# Amp.net
KiCad netlist of a schematic drawn in Altium Designer
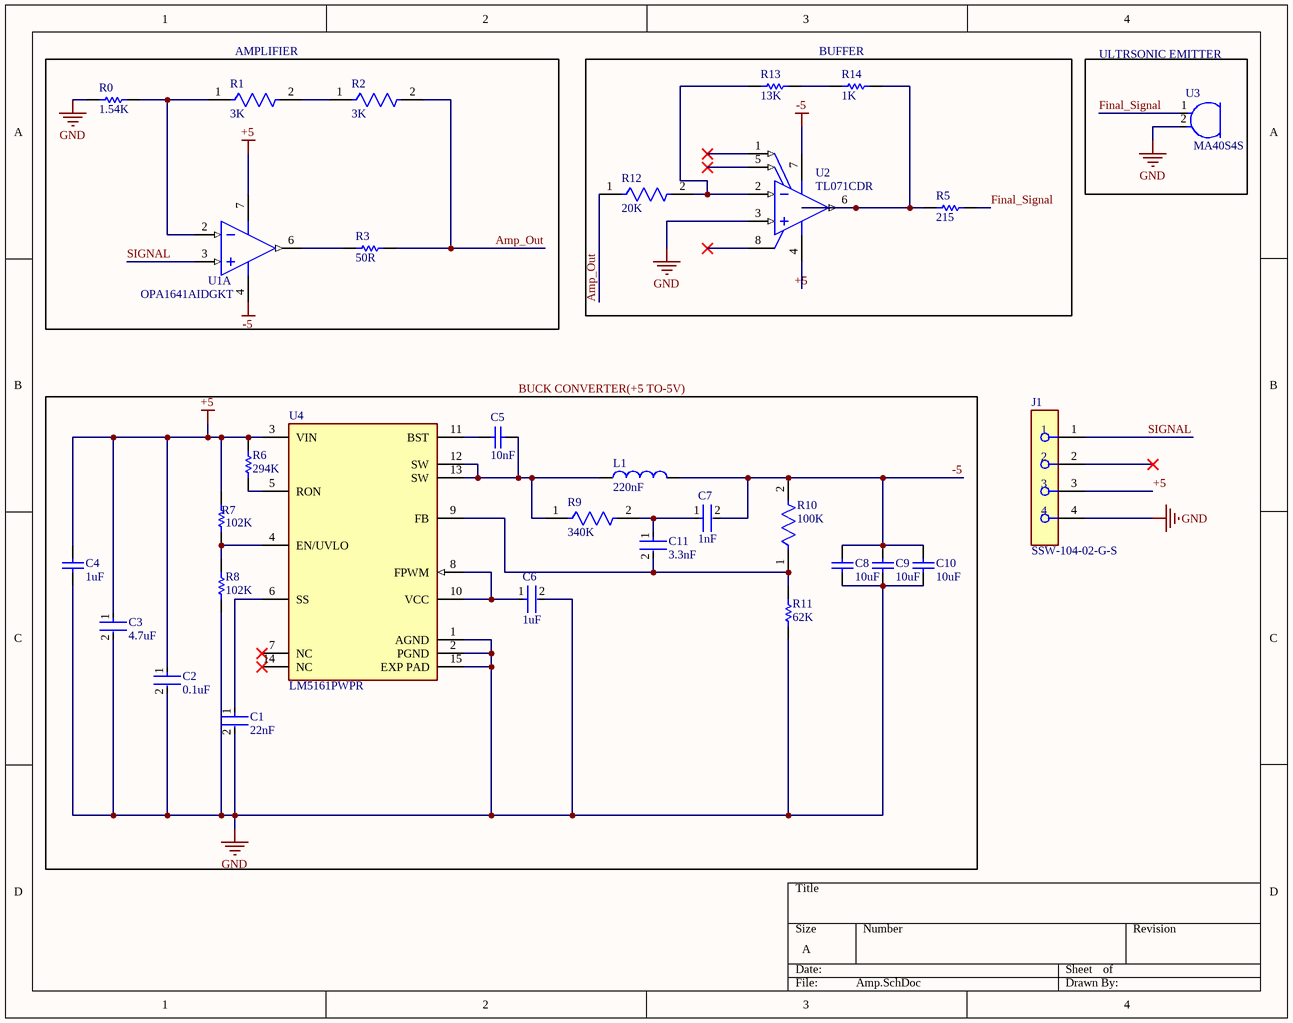
[diagram p0: Amp.SchDoc]

(export (version "E")
  (design (tool "Eeschema 10.0.6"))
  (components
    (comp (ref "C1")
      (value "22nF")
      (footprint "FP-CGA4J-MFG")
      (description "Cap Ceramic 22nF 50V C0G 5% Pad SMD 0805 +125°C Automotive T/R")
      (fields (field (name "TOLERANCE") "5%"))
      (libsource (lib "Altium Content Vault") (part "b4654b650e69147ec39a6b967a45e02"))
    )
    (comp (ref "C2")
      (value "0.1uF")
      (footprint "FP-CC0805-0_85-MFG")
      (description "CAP CER 0.1UF 25V X7R 0805")
      (fields (field (name "MANUFACTURER PART NUMBER") "CC0805KRX7R8BB104") (field (name "TOLERANCE") "0.1"))
      (libsource (lib "Altium Content Vault") (part "11868f565c42a9108669ba33697ecf6"))
    )
    (comp (ref "C3")
      (value "4.7uF")
      (footprint "FP-GRM31C-0_2-e0_3_0_8-IPC_C")
      (description "Chip Multilayer Ceramic Capacitors for General Purpose, 1206, 4.7uF, X7R, 15%, 10%, 50V")
      (fields (field (name "VOLTAGE") "50V") (field (name "TOLERANCE") "10%"))
      (libsource (lib "Altium Content Vault") (part "02cd4be3c70576c341d710602a673aa"))
    )
    (comp (ref "C4")
      (value "1uF")
      (footprint "CAPC3216X180X50ML20T25")
      (description "Chip Capacitor, 1 uF, +/- 10%, 25 V, -55 to 125 degC, 1206 (3216 Metric), RoHS, Tape and Reel")
      (fields (field (name "MANUFACTURER") "Kemet") (field (name "TOLERANCE") "10%"))
      (libsource (lib "Altium Content Vault") (part "CAP-NP-2"))
    )
    (comp (ref "C5")
      (value "10nF")
      (footprint "CAPC1005X55X25LL05T10")
      (description "Chip Capacitor, 10 nF, 16 V, 10%, -55 to 125 degC, 0402 (1005 Metric), RoHS, Tape and Reel")
      (fields (field (name "MANUFACTURER") "Murata"))
      (libsource (lib "Altium Content Vault") (part "CAP-NP-2"))
    )
    (comp (ref "C6")
      (value "1uF")
      (footprint "FP-CGA3E-0_3-0_1-MFG")
      (description "Cap Ceramic 1uF 35V X7R 10% Pad SMD 0603 +125°C Automotive T/R")
      (fields (field (name "TOLERANCE") "10%"))
      (libsource (lib "Altium Content Vault") (part "b4654b650e69147ec39a6b967a45e02"))
    )
    (comp (ref "C7")
      (value "1nF")
      (footprint "FP-CGA2B-MFG")
      (description "Cap Ceramic 1nF 50V X7R 10% Pad SMD 0402 +125°C Automotive T/R")
      (fields (field (name "TOLERANCE") "10%"))
      (libsource (lib "Altium Content Vault") (part "b4654b650e69147ec39a6b967a45e02"))
    )
    (comp (ref "C8")
      (value "10uF")
      (footprint "CAPC3216X180X55LL20T25")
      (description "Chip Capacitor, 10 uF, +/- 10%, 16 V, -55 to 125 degC, 1206 (3216 Metric), RoHS, Tape and Reel")
      (fields (field (name "MANUFACTURER") "Murata") (field (name "TOLERANCE") "±10%"))
      (libsource (lib "Altium Content Vault") (part "CAP-NP-2"))
    )
    (comp (ref "C9")
      (value "10uF")
      (footprint "CAPC3216X180X55LL20T25")
      (description "Chip Capacitor, 10 uF, +/- 10%, 16 V, -55 to 125 degC, 1206 (3216 Metric), RoHS, Tape and Reel")
      (fields (field (name "MANUFACTURER") "Murata") (field (name "TOLERANCE") "±10%"))
      (libsource (lib "Altium Content Vault") (part "CAP-NP-2"))
    )
    (comp (ref "C10")
      (value "10uF")
      (footprint "CAPC3216X180X55LL20T25")
      (description "Chip Capacitor, 10 uF, +/- 10%, 16 V, -55 to 125 degC, 1206 (3216 Metric), RoHS, Tape and Reel")
      (fields (field (name "MANUFACTURER") "Murata") (field (name "TOLERANCE") "±10%"))
      (libsource (lib "Altium Content Vault") (part "CAP-NP-2"))
    )
    (comp (ref "C11")
      (value "3.3nF")
      (footprint "FP-CL31-IPC_C")
      (description "Cap Ceramic 3.3nF 50V X7R ±10% SMD 1206 +125°C Embossed T/R")
      (fields (field (name "TOLERANCE") "10%") (field (name "VOLTAGE") "50V"))
      (libsource (lib "Altium Content Vault") (part "b4654b650e69147ec39a6b967a45e02"))
    )
    (comp (ref "J1")
      (value "SSW-104-02-G-S")
      (footprint "FP-SSW-104-02-G-S-MFG")
      (libsource (lib "Altium Content Vault") (part "56792406a6bd5c25e158f553ecd1aa7"))
    )
    (comp (ref "L1")
      (value "220nF")
      (footprint "WE-HCF_2920")
      (description "74437529203221 WE-HCF High Current Inductor, 220uH, 8.8A, 2.8MHz, 36.45mOhm")
      (libsource (lib "Altium Content Vault") (part "Inductor - 1"))
    )
    (comp (ref "R0")
      (value "1.54K")
      (footprint "RESC2013X70X40LL20T20")
      (fields (field (name "MANUFACTURER") "Panasonic") (field (name "PART NUMBER") "ERJ-6ENF1541V"))
      (libsource (lib "Altium Content Vault") (part "RES"))
    )
    (comp (ref "R1")
      (value "3K")
      (footprint "FP-RC2012-MFG")
      (description "Res Thick Film 0805 3kΩ 1% 0.125W ±100ppm/°C Molded SMD T/R")
      (fields (field (name "TOLERANCE") "1%"))
      (libsource (lib "Altium Content Vault") (part "1029c3af85768c4190bb7ad29bc67b5"))
    )
    (comp (ref "R2")
      (value "3K")
      (footprint "FP-RC2012-MFG")
      (description "Res Thick Film 0805 3kΩ 1% 0.125W ±100ppm/°C Molded SMD T/R")
      (fields (field (name "TOLERANCE") "1%"))
      (libsource (lib "Altium Content Vault") (part "1029c3af85768c4190bb7ad29bc67b5"))
    )
    (comp (ref "R3")
      (value "50R")
      (footprint "RESC2013X70X40LL20T20")
      (fields (field (name "PART NUMBER") "ERJ-6GEYJ510V") (field (name "MANUFACTURER") "Panasonic"))
      (libsource (lib "Altium Content Vault") (part "RES"))
    )
    (comp (ref "R5")
      (value "215")
      (footprint "RESC2013X70X40NL20T20")
      (fields (field (name "MANUFACTURER") "Panasonic") (field (name "PART NUMBER") "ERJ-6ENF2150V"))
      (libsource (lib "Altium Content Vault") (part "RES"))
    )
    (comp (ref "R6")
      (value "294K")
      (footprint "RESC1005X40X25LL05T05")
      (fields (field (name "PART NUMBER") "CRCW0402294KFKED") (field (name "MANUFACTURER") "Vishay Dale"))
      (libsource (lib "Altium Content Vault") (part "RES"))
    )
    (comp (ref "R7")
      (value "102K")
      (footprint "RESC2013X60X35LL10T20")
      (fields (field (name "PART NUMBER") "RC0805FR-07105KL") (field (name "MANUFACTURER") "Yageo"))
      (libsource (lib "Altium Content Vault") (part "RES"))
    )
    (comp (ref "R8")
      (value "102K")
      (footprint "RESC2013X60X35LL10T20")
      (fields (field (name "PART NUMBER") "RC0805FR-07105KL") (field (name "MANUFACTURER") "Yageo"))
      (libsource (lib "Altium Content Vault") (part "RES"))
    )
    (comp (ref "R9")
      (value "340K")
      (footprint "FP-CRCW0402-e3-MFG")
      (description "RES Thick Film, 340kΩ, 1%, 0.063W, 100ppm/°C, 0402")
      (fields (field (name "TOLERANCE") "1%"))
      (libsource (lib "Altium Content Vault") (part "1029c3af85768c4190bb7ad29bc67b5"))
    )
    (comp (ref "R10")
      (value "100K")
      (footprint "FP-RC0603-0_55-MFG")
      (description "RES SMD 100K OHM 1% 1/10W 0603")
      (fields (field (name "TOLERANCE") "1%"))
      (libsource (lib "Altium Content Vault") (part "1029c3af85768c4190bb7ad29bc67b5"))
    )
    (comp (ref "R11")
      (value "62K")
      (footprint "RESC1608X55X25NL10T15")
      (fields (field (name "MANUFACTURER") "Yageo") (field (name "PART NUMBER") "RC0603FR-0762KL"))
      (libsource (lib "Altium Content Vault") (part "RES"))
    )
    (comp (ref "R12")
      (value "20K")
      (footprint "FP-RT0805-MFG")
      (description "RES SMD 20K OHM 1% 1/8W 0805")
      (fields
        (field (name "MANUFACTURER") "Yageo")
        (field (name "MANUFACTURER PART NUMBER") "RT0805FRE0720KL")
      )
      (libsource (lib "Altium Content Vault") (part "1029c3af85768c4190bb7ad29bc67b5"))
    )
    (comp (ref "R13")
      (value "13K")
      (footprint "RESC2013X70X40NL20T20")
      (fields (field (name "PART NUMBER") "ERJ-6ENF1302V") (field (name "MANUFACTURER") "Panasonic"))
      (libsource (lib "Altium Content Vault") (part "RES"))
    )
    (comp (ref "R14")
      (value "1K")
      (footprint "RESC2013X70X40ML20T20")
      (description "Chip Resistor, 1 KOhm, +/- 1%, 0.125 W, -55 to 155 degC, 0805 (2012 Metric), RoHS, Tape and Reel")
      (fields (field (name "MANUFACTURER") "Panasonic"))
      (libsource (lib "Altium Content Vault") (part "RES-2"))
    )
    (comp (ref "U1")
      (value "OPA1641AIDGKT")
      (footprint "DGK0008A_N")
      (fields (field (name "MANUFACTURER") "Texas Instruments"))
      (libsource (lib "Altium Content Vault") (part "TI-OPA1641DGK8"))
    )
    (comp (ref "U2")
      (value "TL071CDR")
      (footprint "D0008A_M")
      (fields (field (name "MANUFACTURER") "Texas Instruments"))
      (libsource (lib "Altium Content Vault") (part "TI-AMP-S5-2-8"))
    )
    (comp (ref "U3")
      (value "MA40S4S")
      (footprint "FP-MA40S4S-MFG")
      (description "ULTRASONIC SENSOR TRANS 40KHZ")
      (libsource (lib "Altium Content Vault") (part "1b72337432ad8929c0ae54f99eb68d9"))
    )
    (comp (ref "U4")
      (value "LM5161PWPR")
      (footprint "FP-PWP0014A-MFG")
      (description "IC REG BCK FLYBCK ADJ 14HTSSOP")
      (fields
        (field (name "MANUFACTURER") "Texas Instruments")
        (field (name "OCTOPART") "https://octopart.com/lm5161pwpr-texas+instruments-71776617")
      )
      (libsource (lib "Altium Content Vault") (part "e7b9f7e172b87fa1c03ad1d8cdbab3b"))
    )
  )
  (nets
    (net (code "1") (name "+5") (class "Default")
      (node (ref "C2") (pin "1") (pinfunction "1_1") (pintype "passive"))
      (node (ref "C3") (pin "1") (pinfunction "1_1") (pintype "passive"))
      (node (ref "C4") (pin "2") (pinfunction "2_2") (pintype "passive"))
      (node (ref "J1") (pin "3") (pinfunction "3_3") (pintype "passive"))
      (node (ref "R6") (pin "2") (pinfunction "2_2") (pintype "passive"))
      (node (ref "R7") (pin "2") (pinfunction "2_2") (pintype "passive"))
      (node (ref "U1") (pin "7") (pinfunction "V+_7") (pintype "power_in"))
      (node (ref "U2") (pin "4") (pinfunction "VCC-_4") (pintype "power_in"))
      (node (ref "U4") (pin "3") (pinfunction "VIN_3") (pintype "power_in"))
    )
    (net (code "2") (name "-5") (class "Default")
      (node (ref "C10") (pin "1") (pinfunction "1_1") (pintype "passive"))
      (node (ref "C7") (pin "2") (pinfunction "2_2") (pintype "passive"))
      (node (ref "C8") (pin "1") (pinfunction "1_1") (pintype "passive"))
      (node (ref "C9") (pin "1") (pinfunction "1_1") (pintype "passive"))
      (node (ref "L1") (pin "2") (pinfunction "2_2") (pintype "passive"))
      (node (ref "R10") (pin "2") (pinfunction "2_2") (pintype "passive"))
      (node (ref "U1") (pin "4") (pinfunction "V-_4") (pintype "power_in"))
      (node (ref "U2") (pin "7") (pinfunction "VCC+_7") (pintype "power_in"))
    )
    (net (code "3") (name "/Amp_Out") (class "Default")
      (node (ref "R12") (pin "1") (pinfunction "1_1") (pintype "passive"))
      (node (ref "R2") (pin "2") (pinfunction "2_2") (pintype "passive"))
      (node (ref "R3") (pin "2") (pinfunction "2_2") (pintype "passive"))
    )
    (net (code "5") (name "/Final_Signal") (class "Default")
      (node (ref "R5") (pin "2") (pinfunction "2_2") (pintype "passive"))
      (node (ref "U3") (pin "1") (pinfunction "1_1") (pintype "passive"))
    )
    (net (code "6") (name "/SIGNAL") (class "Default")
      (node (ref "J1") (pin "1") (pinfunction "1_1") (pintype "passive"))
      (node (ref "U1") (pin "3") (pinfunction "IN+_3") (pintype "input"))
    )
    (net (code "7") (name "GND") (class "Default")
      (node (ref "C1") (pin "2") (pinfunction "2_2") (pintype "passive"))
      (node (ref "C10") (pin "2") (pinfunction "2_2") (pintype "passive"))
      (node (ref "C2") (pin "2") (pinfunction "2_2") (pintype "passive"))
      (node (ref "C3") (pin "2") (pinfunction "2_2") (pintype "passive"))
      (node (ref "C4") (pin "1") (pinfunction "1_1") (pintype "passive"))
      (node (ref "C6") (pin "2") (pinfunction "2_2") (pintype "passive"))
      (node (ref "C8") (pin "2") (pinfunction "2_2") (pintype "passive"))
      (node (ref "C9") (pin "2") (pinfunction "2_2") (pintype "passive"))
      (node (ref "J1") (pin "4") (pinfunction "4_4") (pintype "passive"))
      (node (ref "R0") (pin "1") (pinfunction "1_1") (pintype "passive"))
      (node (ref "R11") (pin "1") (pinfunction "1_1") (pintype "passive"))
      (node (ref "R8") (pin "1") (pinfunction "1_1") (pintype "passive"))
      (node (ref "U2") (pin "3") (pinfunction "IN+_3") (pintype "input"))
      (node (ref "U3") (pin "2") (pinfunction "2_2") (pintype "passive"))
      (node (ref "U4") (pin "1") (pinfunction "AGND_1") (pintype "power_in"))
      (node (ref "U4") (pin "15") (pinfunction "EXP_PAD_15") (pintype "power_in"))
      (node (ref "U4") (pin "2") (pinfunction "PGND_2") (pintype "power_in"))
    )
    (net (code "8") (name "Net-(C5-Pad2)") (class "Default")
      (node (ref "C5") (pin "2") (pinfunction "2_2") (pintype "passive"))
      (node (ref "L1") (pin "1") (pinfunction "1_1") (pintype "passive"))
      (node (ref "R9") (pin "1") (pinfunction "1_1") (pintype "passive"))
      (node (ref "U4") (pin "12") (pinfunction "SW_12") (pintype "passive"))
      (node (ref "U4") (pin "13") (pinfunction "SW_13") (pintype "passive"))
    )
    (net (code "9") (name "Net-(C11-Pad1)") (class "Default")
      (node (ref "C11") (pin "1") (pinfunction "1_1") (pintype "passive"))
      (node (ref "C7") (pin "1") (pinfunction "1_1") (pintype "passive"))
      (node (ref "R9") (pin "2") (pinfunction "2_2") (pintype "passive"))
    )
    (net (code "10") (name "Net-(R1-Pad2)") (class "Default")
      (node (ref "R1") (pin "2") (pinfunction "2_2") (pintype "passive"))
      (node (ref "R2") (pin "1") (pinfunction "1_1") (pintype "passive"))
    )
    (net (code "11") (name "Net-(R13-Pad2)") (class "Default")
      (node (ref "R13") (pin "2") (pinfunction "2_2") (pintype "passive"))
      (node (ref "R14") (pin "1") (pinfunction "1_1") (pintype "passive"))
    )
    (net (code "12") (name "Net-(U1A-IN-)") (class "Default")
      (node (ref "R0") (pin "2") (pinfunction "2_2") (pintype "passive"))
      (node (ref "R1") (pin "1") (pinfunction "1_1") (pintype "passive"))
      (node (ref "U1") (pin "2") (pinfunction "IN-_2") (pintype "input"))
    )
    (net (code "13") (name "Net-(U1A-OUT)") (class "Default")
      (node (ref "R3") (pin "1") (pinfunction "1_1") (pintype "passive"))
      (node (ref "U1") (pin "6") (pinfunction "OUT_6") (pintype "output"))
    )
    (net (code "14") (name "Net-(U2-IN-)") (class "Default")
      (node (ref "R12") (pin "2") (pinfunction "2_2") (pintype "passive"))
      (node (ref "R13") (pin "1") (pinfunction "1_1") (pintype "passive"))
      (node (ref "U2") (pin "2") (pinfunction "IN-_2") (pintype "input"))
    )
    (net (code "15") (name "Net-(U2-OUT)") (class "Default")
      (node (ref "R14") (pin "2") (pinfunction "2_2") (pintype "passive"))
      (node (ref "R5") (pin "1") (pinfunction "1_1") (pintype "passive"))
      (node (ref "U2") (pin "6") (pinfunction "OUT_6") (pintype "output"))
    )
    (net (code "16") (name "Net-(U4-BST)") (class "Default")
      (node (ref "C5") (pin "1") (pinfunction "1_1") (pintype "passive"))
      (node (ref "U4") (pin "11") (pinfunction "BST_11") (pintype "passive"))
    )
    (net (code "17") (name "Net-(U4-EN{slash}UVLO)") (class "Default")
      (node (ref "R7") (pin "1") (pinfunction "1_1") (pintype "passive"))
      (node (ref "R8") (pin "2") (pinfunction "2_2") (pintype "passive"))
      (node (ref "U4") (pin "4") (pinfunction "EN/UVLO_4") (pintype "passive"))
    )
    (net (code "18") (name "Net-(U4-FB)") (class "Default")
      (node (ref "C11") (pin "2") (pinfunction "2_2") (pintype "passive"))
      (node (ref "R10") (pin "1") (pinfunction "1_1") (pintype "passive"))
      (node (ref "R11") (pin "2") (pinfunction "2_2") (pintype "passive"))
      (node (ref "U4") (pin "9") (pinfunction "FB_9") (pintype "passive"))
    )
    (net (code "19") (name "Net-(U4-FPWM)") (class "Default")
      (node (ref "C6") (pin "1") (pinfunction "1_1") (pintype "passive"))
      (node (ref "U4") (pin "10") (pinfunction "VCC_10") (pintype "passive"))
      (node (ref "U4") (pin "8") (pinfunction "FPWM_8") (pintype "input"))
    )
    (net (code "20") (name "Net-(U4-RON)") (class "Default")
      (node (ref "R6") (pin "1") (pinfunction "1_1") (pintype "passive"))
      (node (ref "U4") (pin "5") (pinfunction "RON_5") (pintype "passive"))
    )
    (net (code "21") (name "Net-(U4-SS)") (class "Default")
      (node (ref "C1") (pin "1") (pinfunction "1_1") (pintype "passive"))
      (node (ref "U4") (pin "6") (pinfunction "SS_6") (pintype "passive"))
    )
    (net (code "22") (name "unconnected-(J1-Pad2)") (class "Default")
      (node (ref "J1") (pin "2") (pinfunction "2_2") (pintype "passive+no_connect"))
    )
    (net (code "23") (name "unconnected-(U2-NC-Pad8)") (class "Default")
      (node (ref "U2") (pin "8") (pinfunction "NC_8") (pintype "passive+no_connect"))
    )
    (net (code "24") (name "unconnected-(U2-OFFSET_N1-Pad1)") (class "Default")
      (node (ref "U2") (pin "1") (pinfunction "OFFSET_N1_1") (pintype "input+no_connect"))
    )
    (net (code "25") (name "unconnected-(U2-OFFSET_N2-Pad5)") (class "Default")
      (node (ref "U2") (pin "5") (pinfunction "OFFSET_N2_5") (pintype "input+no_connect"))
    )
    (net (code "26") (name "unconnected-(U4-NC-Pad7)") (class "Default")
      (node (ref "U4") (pin "7") (pinfunction "NC_7") (pintype "passive+no_connect"))
    )
    (net (code "27") (name "unconnected-(U4-NC-Pad14)") (class "Default")
      (node (ref "U4") (pin "14") (pinfunction "NC_14") (pintype "passive+no_connect"))
    )
  )
)
